# dcshift.net
KiCad netlist of a schematic drawn in Altium Designer
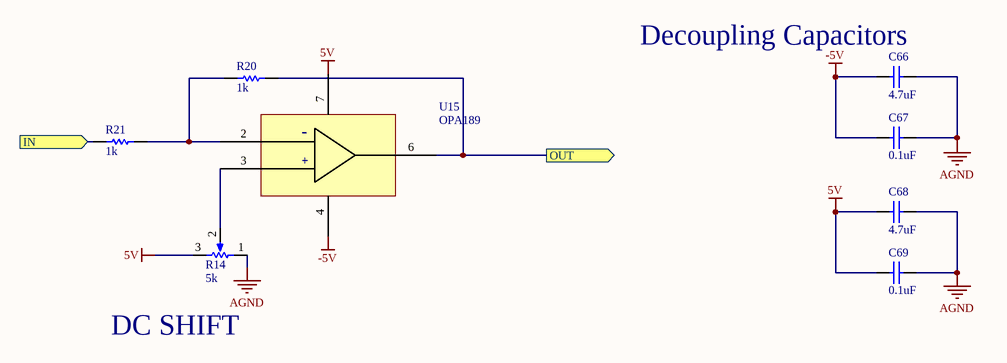
[diagram p0: dcshift.SchDoc]

(export (version "E")
  (design (tool "Eeschema 10.0.6"))
  (components
    (comp (ref "C66")
      (value "4.7uF")
      (footprint "0402_Cap")
      (description "Capacitor, 4.7uF, 0805")
      (libsource (lib "Arturo_Approved") (part "CL21A475KAQNNNE"))
    )
    (comp (ref "C67")
      (value "0.1uF")
      (footprint "0402_Cap")
      (description "Capacitor, 0.1uF, 0805")
      (libsource (lib "Arturo_Approved") (part "CL21B104KACNNNC"))
    )
    (comp (ref "C68")
      (value "4.7uF")
      (footprint "0402_Cap")
      (description "Capacitor, 4.7uF, 0805")
      (libsource (lib "Arturo_Approved") (part "CL21A475KAQNNNE"))
    )
    (comp (ref "C69")
      (value "0.1uF")
      (footprint "0402_Cap")
      (description "Capacitor, 0.1uF, 0805")
      (libsource (lib "Arturo_Approved") (part "CL21B104KACNNNC"))
    )
    (comp (ref "R14")
      (value "5k")
      (footprint "TRIMPOT")
      (description "Potentiometer, 1k")
      (libsource (lib "Arturo_Approved") (part "PV36W102C01B00"))
    )
    (comp (ref "R20")
      (value "1k")
      (footprint "0402_Res")
      (description "1K 1% 1/4W")
      (libsource (lib "Arturo_Approved") (part "RNCP0805FTD1K00"))
    )
    (comp (ref "R21")
      (value "1k")
      (footprint "0402_Res")
      (description "1K 1% 1/4W")
      (libsource (lib "Arturo_Approved") (part "RNCP0805FTD1K00"))
    )
    (comp (ref "U15")
      (value "OPA189")
      (footprint "SOIC_8")
      (description "Precision OpAmp, Generic")
      (libsource (lib "Arturo_Approved") (part "OPA189IDR"))
    )
  )
  (nets
    (net (code "1") (name "-5V") (class "Default")
      (node (ref "C66") (pin "1") (pinfunction "1_1") (pintype "passive"))
      (node (ref "C67") (pin "1") (pinfunction "1_1") (pintype "passive"))
      (node (ref "U15") (pin "4") (pintype "passive"))
    )
    (net (code "2") (name "/IN") (class "Default")
      (node (ref "R21") (pin "1") (pinfunction "1_1") (pintype "passive"))
    )
    (net (code "3") (name "/OUT") (class "Default")
      (node (ref "R20") (pin "2") (pinfunction "2_2") (pintype "passive"))
      (node (ref "U15") (pin "6") (pintype "passive"))
    )
    (net (code "4") (name "5V") (class "Default")
      (node (ref "C68") (pin "1") (pinfunction "1_1") (pintype "passive"))
      (node (ref "C69") (pin "1") (pinfunction "1_1") (pintype "passive"))
      (node (ref "R14") (pin "3") (pinfunction "BOT_3") (pintype "passive"))
      (node (ref "U15") (pin "7") (pintype "passive"))
    )
    (net (code "5") (name "AGND") (class "Default")
      (node (ref "C66") (pin "2") (pinfunction "2_2") (pintype "passive"))
      (node (ref "C67") (pin "2") (pinfunction "2_2") (pintype "passive"))
      (node (ref "C68") (pin "2") (pinfunction "2_2") (pintype "passive"))
      (node (ref "C69") (pin "2") (pinfunction "2_2") (pintype "passive"))
      (node (ref "R14") (pin "1") (pinfunction "TOP_1") (pintype "passive"))
    )
    (net (code "6") (name "Net-(R14-TAP)") (class "Default")
      (node (ref "R14") (pin "2") (pinfunction "TAP_2") (pintype "passive"))
      (node (ref "U15") (pin "3") (pintype "passive"))
    )
    (net (code "7") (name "Net-(R20-Pad1)") (class "Default")
      (node (ref "R20") (pin "1") (pinfunction "1_1") (pintype "passive"))
      (node (ref "R21") (pin "2") (pinfunction "2_2") (pintype "passive"))
      (node (ref "U15") (pin "2") (pintype "passive"))
    )
  )
)
